# DDR3.net
KiCad netlist of a schematic drawn in Altium Designer
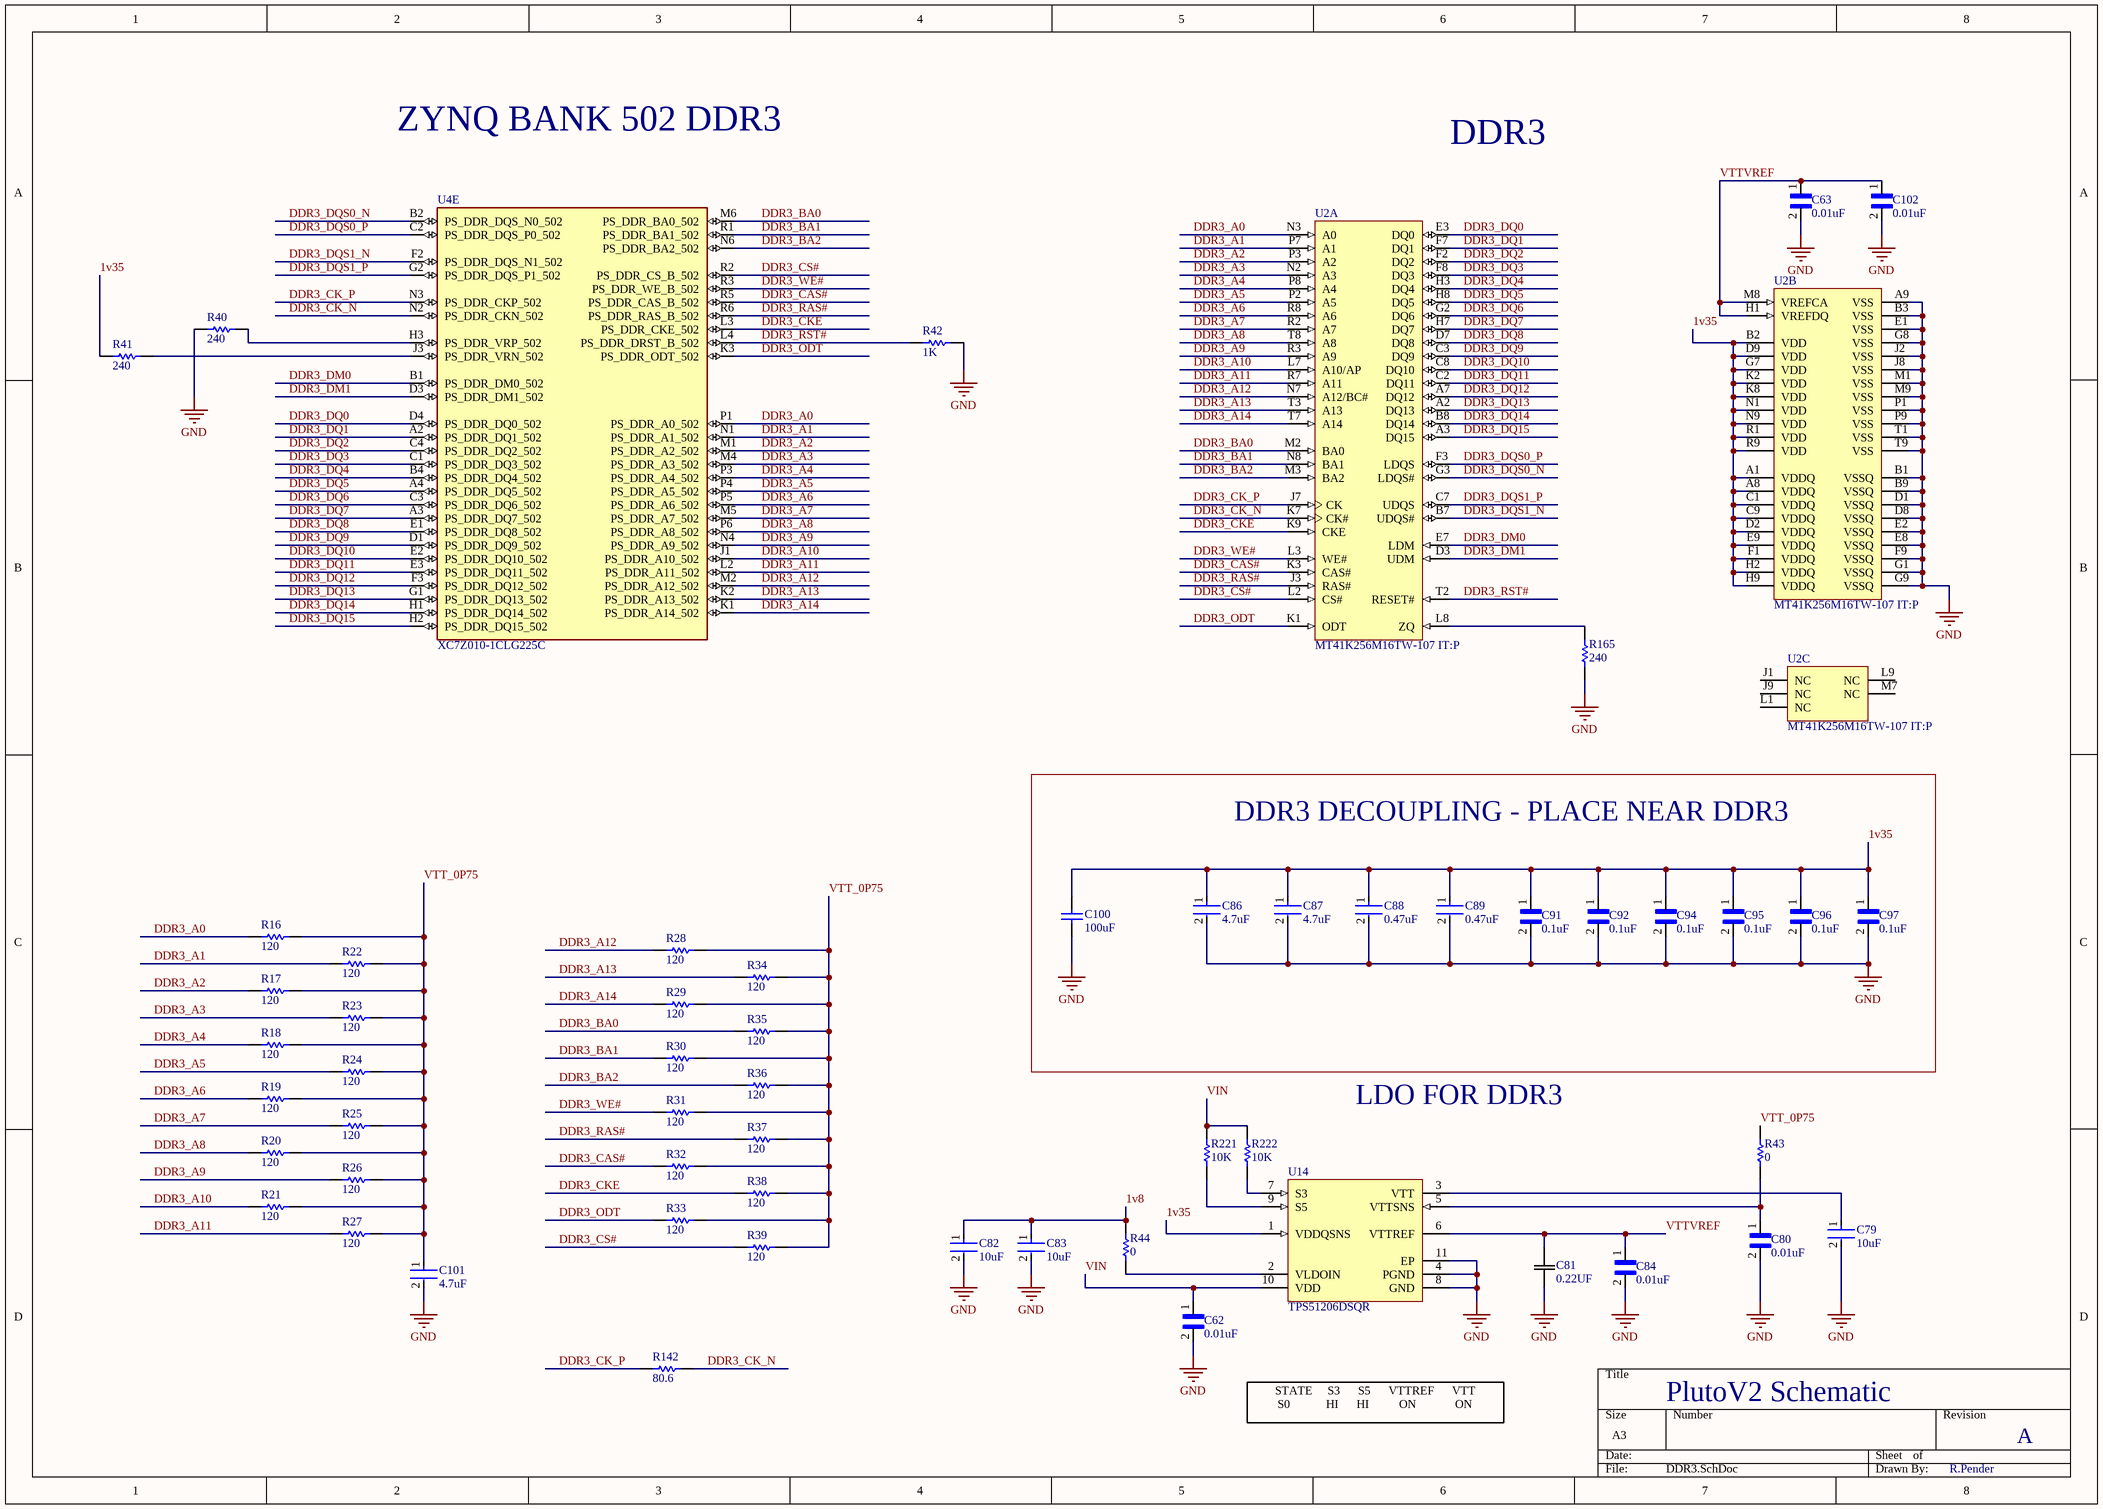
[diagram p0: DDR3.SchDoc]

(export (version "E")
  (design (tool "Eeschema 10.0.6"))
  (components
    (comp (ref "C62")
      (value "0.01uF")
      (footprint "CAPC0603X33N")
      (description "SMD Capacitor X7R(EIA) with Capacitance: 10000pF Tol. 10%. Rated Voltage: 10Vdc")
      (fields (field (name "MP") "GRM033R71A103KA01D") (field (name "MF") "Murata"))
      (libsource (lib "GRM033R71A103KA01D") (part "GRM033R71A103KA01D"))
    )
    (comp (ref "C63")
      (value "0.01uF")
      (footprint "CAPC0603X33N")
      (description "SMD Capacitor X7R(EIA) with Capacitance: 10000pF Tol. 10%. Rated Voltage: 10Vdc")
      (fields (field (name "MP") "GRM033R71A103KA01D") (field (name "MF") "Murata"))
      (libsource (lib "GRM033R71A103KA01D") (part "GRM033R71A103KA01D"))
    )
    (comp (ref "C79")
      (value "10uF")
      (footprint "FP-GRM188-0_1-e0_2_0_55-IPC_A")
      (description "Chip Multilayer Ceramic Capacitors for General Purpose, 0603, 10uF, X5R, 15%, 20%, 6.3V")
      (fields (field (name "VOLTAGE") "6.3V") (field (name "TOLERANCE") "20%"))
      (libsource (lib "Altium Content Vault") (part "02cd4be3c70576c341d710602a673aa"))
    )
    (comp (ref "C80")
      (value "0.01uF")
      (footprint "CAPC0603X33N")
      (description "SMD Capacitor X7R(EIA) with Capacitance: 10000pF Tol. 10%. Rated Voltage: 10Vdc")
      (fields (field (name "MP") "GRM033R71A103KA01D") (field (name "MF") "Murata"))
      (libsource (lib "GRM033R71A103KA01D") (part "GRM033R71A103KA01D"))
    )
    (comp (ref "C81")
      (value "0.22UF")
      (footprint "CAP_U_0805_KNO")
      (description "No Description Available")
      (fields
        (field (name "MANUFACTURER_PART_NUMBER") "080530250224KXT")
        (field (name "COPYRIGHT") "Copyright (C) 2022 Ultra Librarian. All rights reserved.")
      )
      (libsource (lib "080530250224KXT") (part "080530250224KXT"))
    )
    (comp (ref "C82")
      (value "10uF")
      (footprint "FP-GRM188-0_1-e0_2_0_55-IPC_A")
      (description "Chip Multilayer Ceramic Capacitors for General Purpose, 0603, 10uF, X5R, 15%, 20%, 6.3V")
      (fields (field (name "VOLTAGE") "6.3V") (field (name "TOLERANCE") "20%"))
      (libsource (lib "Altium Content Vault") (part "02cd4be3c70576c341d710602a673aa"))
    )
    (comp (ref "C83")
      (value "10uF")
      (footprint "FP-GRM188-0_1-e0_2_0_55-IPC_A")
      (description "Chip Multilayer Ceramic Capacitors for General Purpose, 0603, 10uF, X5R, 15%, 20%, 6.3V")
      (fields (field (name "VOLTAGE") "6.3V") (field (name "TOLERANCE") "20%"))
      (libsource (lib "Altium Content Vault") (part "02cd4be3c70576c341d710602a673aa"))
    )
    (comp (ref "C84")
      (value "0.01uF")
      (footprint "CAPC0603X33N")
      (description "SMD Capacitor X7R(EIA) with Capacitance: 10000pF Tol. 10%. Rated Voltage: 10Vdc")
      (fields (field (name "MP") "GRM033R71A103KA01D") (field (name "MF") "Murata"))
      (libsource (lib "GRM033R71A103KA01D") (part "GRM033R71A103KA01D"))
    )
    (comp (ref "C86")
      (value "4.7uF")
      (footprint "FP-C1005-050-0_15-MFG")
      (description "CAP CER 4.7UF 6.3V X5R 0402")
      (fields (field (name "VOLTAGE") "6.3V") (field (name "TOLERANCE") "10%"))
      (libsource (lib "Altium Content Vault") (part "02cd4be3c70576c341d710602a673aa"))
    )
    (comp (ref "C87")
      (value "4.7uF")
      (footprint "FP-C1005-050-0_15-MFG")
      (description "CAP CER 4.7UF 6.3V X5R 0402")
      (fields (field (name "VOLTAGE") "6.3V") (field (name "TOLERANCE") "10%"))
      (libsource (lib "Altium Content Vault") (part "02cd4be3c70576c341d710602a673aa"))
    )
    (comp (ref "C88")
      (value "0.47uF")
      (footprint "FP-C1005-050-0_15-MFG")
      (description "CAP CER 4.7UF 6.3V X5R 0402")
      (fields (field (name "VOLTAGE") "6.3V") (field (name "TOLERANCE") "10%"))
      (libsource (lib "Altium Content Vault") (part "02cd4be3c70576c341d710602a673aa"))
    )
    (comp (ref "C89")
      (value "0.47uF")
      (footprint "FP-C1005-050-0_15-MFG")
      (description "CAP CER 4.7UF 6.3V X5R 0402")
      (fields (field (name "VOLTAGE") "6.3V") (field (name "TOLERANCE") "10%"))
      (libsource (lib "Altium Content Vault") (part "02cd4be3c70576c341d710602a673aa"))
    )
    (comp (ref "C91")
      (value "0.1uF")
      (footprint "CAPC0603X33N")
      (description "CAP 0.1UF 16VDC X5R 20% SMD 0201 PAPER TAPE")
      (fields (field (name "MP") "GRM033R61C104ME84D"))
      (libsource (lib "GRM033R61C104ME84D") (part "GRM033R61C104ME84D"))
    )
    (comp (ref "C92")
      (value "0.1uF")
      (footprint "CAPC0603X33N")
      (description "CAP 0.1UF 16VDC X5R 20% SMD 0201 PAPER TAPE")
      (fields (field (name "MP") "GRM033R61C104ME84D"))
      (libsource (lib "GRM033R61C104ME84D") (part "GRM033R61C104ME84D"))
    )
    (comp (ref "C94")
      (value "0.1uF")
      (footprint "CAPC0603X33N")
      (description "CAP 0.1UF 16VDC X5R 20% SMD 0201 PAPER TAPE")
      (fields (field (name "MP") "GRM033R61C104ME84D"))
      (libsource (lib "GRM033R61C104ME84D") (part "GRM033R61C104ME84D"))
    )
    (comp (ref "C95")
      (value "0.1uF")
      (footprint "CAPC0603X33N")
      (description "CAP 0.1UF 16VDC X5R 20% SMD 0201 PAPER TAPE")
      (fields (field (name "MP") "GRM033R61C104ME84D"))
      (libsource (lib "GRM033R61C104ME84D") (part "GRM033R61C104ME84D"))
    )
    (comp (ref "C96")
      (value "0.1uF")
      (footprint "CAPC0603X33N")
      (description "CAP 0.1UF 16VDC X5R 20% SMD 0201 PAPER TAPE")
      (fields (field (name "MP") "GRM033R61C104ME84D"))
      (libsource (lib "GRM033R61C104ME84D") (part "GRM033R61C104ME84D"))
    )
    (comp (ref "C97")
      (value "0.1uF")
      (footprint "CAPC0603X33N")
      (description "CAP 0.1UF 16VDC X5R 20% SMD 0201 PAPER TAPE")
      (fields (field (name "MP") "GRM033R61C104ME84D"))
      (libsource (lib "GRM033R61C104ME84D") (part "GRM033R61C104ME84D"))
    )
    (comp (ref "C100")
      (value "100uF")
      (footprint "CAPC3216X190X55ML30T25")
      (description "Chip Capacitor, 100 uF, +/- 20%, 6.3 V, -55 to 85 degC, 1206 (3216 Metric), RoHS, Tape and Reel")
      (fields (field (name "TOLERANCE") "20%") (field (name "PARTNUMBER") "GRM31CR60J107ME39L"))
      (libsource (lib "Altium Content Vault") (part "CAP-NP-2"))
    )
    (comp (ref "C101")
      (value "4.7uF")
      (footprint "FP-C1005-050-0_15-MFG")
      (description "CAP CER 4.7UF 6.3V X5R 0402")
      (fields (field (name "VOLTAGE") "6.3V") (field (name "TOLERANCE") "10%"))
      (libsource (lib "Altium Content Vault") (part "02cd4be3c70576c341d710602a673aa"))
    )
    (comp (ref "C102")
      (value "0.01uF")
      (footprint "CAPC0603X33N")
      (description "SMD Capacitor X7R(EIA) with Capacitance: 10000pF Tol. 10%. Rated Voltage: 10Vdc")
      (fields (field (name "MP") "GRM033R71A103KA01D") (field (name "MF") "Murata"))
      (libsource (lib "GRM033R71A103KA01D") (part "GRM033R71A103KA01D"))
    )
    (comp (ref "R16")
      (value "120")
      (footprint "1-0201")
      (description "Thick Film Chip Resistor, 10 Ohm to 1M Ohm Range, 5% Tolerance, 0201 Size, 0.05 W")
      (fields (field (name "PUBLISHER") "Altium Limited"))
      (libsource (lib "Panasonic Resistor") (part "ERJ1GE"))
    )
    (comp (ref "R17")
      (value "120")
      (footprint "1-0201")
      (description "Thick Film Chip Resistor, 10 Ohm to 1M Ohm Range, 5% Tolerance, 0201 Size, 0.05 W")
      (fields (field (name "PUBLISHER") "Altium Limited"))
      (libsource (lib "Panasonic Resistor") (part "ERJ1GE"))
    )
    (comp (ref "R18")
      (value "120")
      (footprint "1-0201")
      (description "Thick Film Chip Resistor, 10 Ohm to 1M Ohm Range, 5% Tolerance, 0201 Size, 0.05 W")
      (fields (field (name "PUBLISHER") "Altium Limited"))
      (libsource (lib "Panasonic Resistor") (part "ERJ1GE"))
    )
    (comp (ref "R19")
      (value "120")
      (footprint "1-0201")
      (description "Thick Film Chip Resistor, 10 Ohm to 1M Ohm Range, 5% Tolerance, 0201 Size, 0.05 W")
      (fields (field (name "PUBLISHER") "Altium Limited"))
      (libsource (lib "Panasonic Resistor") (part "ERJ1GE"))
    )
    (comp (ref "R20")
      (value "120")
      (footprint "1-0201")
      (description "Thick Film Chip Resistor, 10 Ohm to 1M Ohm Range, 5% Tolerance, 0201 Size, 0.05 W")
      (fields (field (name "PUBLISHER") "Altium Limited"))
      (libsource (lib "Panasonic Resistor") (part "ERJ1GE"))
    )
    (comp (ref "R21")
      (value "120")
      (footprint "1-0201")
      (description "Thick Film Chip Resistor, 10 Ohm to 1M Ohm Range, 5% Tolerance, 0201 Size, 0.05 W")
      (fields (field (name "PUBLISHER") "Altium Limited"))
      (libsource (lib "Panasonic Resistor") (part "ERJ1GE"))
    )
    (comp (ref "R22")
      (value "120")
      (footprint "1-0201")
      (description "Thick Film Chip Resistor, 10 Ohm to 1M Ohm Range, 5% Tolerance, 0201 Size, 0.05 W")
      (fields (field (name "PUBLISHER") "Altium Limited"))
      (libsource (lib "Panasonic Resistor") (part "ERJ1GE"))
    )
    (comp (ref "R23")
      (value "120")
      (footprint "1-0201")
      (description "Thick Film Chip Resistor, 10 Ohm to 1M Ohm Range, 5% Tolerance, 0201 Size, 0.05 W")
      (fields (field (name "PUBLISHER") "Altium Limited"))
      (libsource (lib "Panasonic Resistor") (part "ERJ1GE"))
    )
    (comp (ref "R24")
      (value "120")
      (footprint "1-0201")
      (description "Thick Film Chip Resistor, 10 Ohm to 1M Ohm Range, 5% Tolerance, 0201 Size, 0.05 W")
      (fields (field (name "PUBLISHER") "Altium Limited"))
      (libsource (lib "Panasonic Resistor") (part "ERJ1GE"))
    )
    (comp (ref "R25")
      (value "120")
      (footprint "1-0201")
      (description "Thick Film Chip Resistor, 10 Ohm to 1M Ohm Range, 5% Tolerance, 0201 Size, 0.05 W")
      (fields (field (name "PUBLISHER") "Altium Limited"))
      (libsource (lib "Panasonic Resistor") (part "ERJ1GE"))
    )
    (comp (ref "R26")
      (value "120")
      (footprint "1-0201")
      (description "Thick Film Chip Resistor, 10 Ohm to 1M Ohm Range, 5% Tolerance, 0201 Size, 0.05 W")
      (fields (field (name "PUBLISHER") "Altium Limited"))
      (libsource (lib "Panasonic Resistor") (part "ERJ1GE"))
    )
    (comp (ref "R27")
      (value "120")
      (footprint "1-0201")
      (description "Thick Film Chip Resistor, 10 Ohm to 1M Ohm Range, 5% Tolerance, 0201 Size, 0.05 W")
      (fields (field (name "PUBLISHER") "Altium Limited"))
      (libsource (lib "Panasonic Resistor") (part "ERJ1GE"))
    )
    (comp (ref "R28")
      (value "120")
      (footprint "1-0201")
      (description "Thick Film Chip Resistor, 10 Ohm to 1M Ohm Range, 5% Tolerance, 0201 Size, 0.05 W")
      (fields (field (name "PUBLISHER") "Altium Limited"))
      (libsource (lib "Panasonic Resistor") (part "ERJ1GE"))
    )
    (comp (ref "R29")
      (value "120")
      (footprint "1-0201")
      (description "Thick Film Chip Resistor, 10 Ohm to 1M Ohm Range, 5% Tolerance, 0201 Size, 0.05 W")
      (fields (field (name "PUBLISHER") "Altium Limited"))
      (libsource (lib "Panasonic Resistor") (part "ERJ1GE"))
    )
    (comp (ref "R30")
      (value "120")
      (footprint "1-0201")
      (description "Thick Film Chip Resistor, 10 Ohm to 1M Ohm Range, 5% Tolerance, 0201 Size, 0.05 W")
      (fields (field (name "PUBLISHER") "Altium Limited"))
      (libsource (lib "Panasonic Resistor") (part "ERJ1GE"))
    )
    (comp (ref "R31")
      (value "120")
      (footprint "1-0201")
      (description "Thick Film Chip Resistor, 10 Ohm to 1M Ohm Range, 5% Tolerance, 0201 Size, 0.05 W")
      (fields (field (name "PUBLISHER") "Altium Limited"))
      (libsource (lib "Panasonic Resistor") (part "ERJ1GE"))
    )
    (comp (ref "R32")
      (value "120")
      (footprint "1-0201")
      (description "Thick Film Chip Resistor, 10 Ohm to 1M Ohm Range, 5% Tolerance, 0201 Size, 0.05 W")
      (fields (field (name "PUBLISHER") "Altium Limited"))
      (libsource (lib "Panasonic Resistor") (part "ERJ1GE"))
    )
    (comp (ref "R33")
      (value "120")
      (footprint "1-0201")
      (description "Thick Film Chip Resistor, 10 Ohm to 1M Ohm Range, 5% Tolerance, 0201 Size, 0.05 W")
      (fields (field (name "PUBLISHER") "Altium Limited"))
      (libsource (lib "Panasonic Resistor") (part "ERJ1GE"))
    )
    (comp (ref "R34")
      (value "120")
      (footprint "1-0201")
      (description "Thick Film Chip Resistor, 10 Ohm to 1M Ohm Range, 5% Tolerance, 0201 Size, 0.05 W")
      (fields (field (name "PUBLISHER") "Altium Limited"))
      (libsource (lib "Panasonic Resistor") (part "ERJ1GE"))
    )
    (comp (ref "R35")
      (value "120")
      (footprint "1-0201")
      (description "Thick Film Chip Resistor, 10 Ohm to 1M Ohm Range, 5% Tolerance, 0201 Size, 0.05 W")
      (fields (field (name "PUBLISHER") "Altium Limited"))
      (libsource (lib "Panasonic Resistor") (part "ERJ1GE"))
    )
    (comp (ref "R36")
      (value "120")
      (footprint "1-0201")
      (description "Thick Film Chip Resistor, 10 Ohm to 1M Ohm Range, 5% Tolerance, 0201 Size, 0.05 W")
      (fields (field (name "PUBLISHER") "Altium Limited"))
      (libsource (lib "Panasonic Resistor") (part "ERJ1GE"))
    )
    (comp (ref "R37")
      (value "120")
      (footprint "1-0201")
      (description "Thick Film Chip Resistor, 10 Ohm to 1M Ohm Range, 5% Tolerance, 0201 Size, 0.05 W")
      (fields (field (name "PUBLISHER") "Altium Limited"))
      (libsource (lib "Panasonic Resistor") (part "ERJ1GE"))
    )
    (comp (ref "R38")
      (value "120")
      (footprint "1-0201")
      (description "Thick Film Chip Resistor, 10 Ohm to 1M Ohm Range, 5% Tolerance, 0201 Size, 0.05 W")
      (fields (field (name "PUBLISHER") "Altium Limited"))
      (libsource (lib "Panasonic Resistor") (part "ERJ1GE"))
    )
    (comp (ref "R39")
      (value "120")
      (footprint "1-0201")
      (description "Thick Film Chip Resistor, 10 Ohm to 1M Ohm Range, 5% Tolerance, 0201 Size, 0.05 W")
      (fields (field (name "PUBLISHER") "Altium Limited"))
      (libsource (lib "Panasonic Resistor") (part "ERJ1GE"))
    )
    (comp (ref "R40")
      (value "240")
      (footprint "2-0402")
      (fields (field (name "PUBLISHER") "Altium Limited"))
      (libsource (lib "Panasonic Resistor") (part "ERJ2RK"))
    )
    (comp (ref "R41")
      (value "240")
      (footprint "2-0402")
      (fields (field (name "PUBLISHER") "Altium Limited"))
      (libsource (lib "Panasonic Resistor") (part "ERJ2RK"))
    )
    (comp (ref "R42")
      (value "1K")
      (footprint "2-0402")
      (fields (field (name "PUBLISHER") "Altium Limited"))
      (libsource (lib "Panasonic Resistor") (part "ERJ2RK"))
    )
    (comp (ref "R43")
      (value "0")
      (footprint "RESC1005X40X25NL10T10")
      (fields (field (name "PART NUMBER") "MC00625W040210R") (field (name "MANUFACTURER") "Multicomp"))
      (libsource (lib "Altium Content Vault") (part "RES"))
    )
    (comp (ref "R44")
      (value "0")
      (footprint "RESC1005X40X25NL10T10")
      (fields (field (name "PART NUMBER") "MC00625W040210R") (field (name "MANUFACTURER") "Multicomp"))
      (libsource (lib "Altium Content Vault") (part "RES"))
    )
    (comp (ref "R142")
      (value "80.6")
      (footprint "2-0402")
      (fields (field (name "PUBLISHER") "Altium Limited"))
      (libsource (lib "Panasonic Resistor") (part "ERJ2RK"))
    )
    (comp (ref "R165")
      (value "240")
      (footprint "2-0402")
      (fields (field (name "PUBLISHER") "Altium Limited"))
      (libsource (lib "Panasonic Resistor") (part "ERJ2RK"))
    )
    (comp (ref "R221")
      (value "10K")
      (footprint "2-0402")
      (fields (field (name "PUBLISHER") "Altium Limited"))
      (libsource (lib "Panasonic Resistor") (part "ERJ2RK"))
    )
    (comp (ref "R222")
      (value "10K")
      (footprint "2-0402")
      (fields (field (name "PUBLISHER") "Altium Limited"))
      (libsource (lib "Panasonic Resistor") (part "ERJ2RK"))
    )
    (comp (ref "U2")
      (value "MT41K256M16TW-107 IT:P")
      (footprint "MICT-TW-96")
      (description "Automotive DDR3L SDRAM, 4 GB, 933 MHz, 1.283 to 1.45 V, -40 to 95 degC, 96-Pin TFBGA, RoHS, Tray")
      (fields (field (name "MANUFACTURER") "Micron"))
      (libsource (lib "Components - 26.05.22 - 21.32") (part "CMP-2000-06773-2"))
    )
    (comp (ref "U4")
      (value "XC7Z010-1CLG225C")
      (footprint "BGA225C80P15X15_1300X1300X150")
      (fields (field (name "MF") "Xilinx Inc.") (field (name "DIGI-KEY_PART_NUMBER") "122-1855-ND"))
      (libsource (lib "XC7Z010-1CLG225C") (part "XC7Z010-1CLG225C"))
    )
    (comp (ref "U14")
      (value "TPS51206DSQR")
      (footprint "DSQ0010A_V")
      (fields (field (name "MANUFACTURER") "Texas Instruments"))
      (libsource (lib "Altium Content Vault") (part "TI-TPS51206DSQ10-1500X900TP"))
    )
  )
  (nets
    (net (code "1") (name "/1v8") (class "Default")
      (node (ref "C82") (pin "1") (pinfunction "1_1") (pintype "passive"))
      (node (ref "C83") (pin "1") (pinfunction "1_1") (pintype "passive"))
      (node (ref "R44") (pin "1") (pinfunction "1_1") (pintype "passive"))
    )
    (net (code "2") (name "/1v35") (class "Default")
      (node (ref "C100") (pin "1") (pinfunction "1_1") (pintype "passive"))
      (node (ref "C86") (pin "1") (pinfunction "1_1") (pintype "passive"))
      (node (ref "C87") (pin "1") (pinfunction "1_1") (pintype "passive"))
      (node (ref "C88") (pin "1") (pinfunction "1_1") (pintype "passive"))
      (node (ref "C89") (pin "1") (pinfunction "1_1") (pintype "passive"))
      (node (ref "C91") (pin "1") (pinfunction "1_1") (pintype "passive"))
      (node (ref "C92") (pin "1") (pinfunction "1_1") (pintype "passive"))
      (node (ref "C94") (pin "1") (pinfunction "1_1") (pintype "passive"))
      (node (ref "C95") (pin "1") (pinfunction "1_1") (pintype "passive"))
      (node (ref "C96") (pin "1") (pinfunction "1_1") (pintype "passive"))
      (node (ref "C97") (pin "1") (pinfunction "1_1") (pintype "passive"))
      (node (ref "R41") (pin "1") (pinfunction "1_1") (pintype "passive"))
      (node (ref "U14") (pin "1") (pinfunction "VDDQSNS_1") (pintype "input"))
      (node (ref "U2") (pin "A1") (pinfunction "VDDQ_A1") (pintype "power_in"))
      (node (ref "U2") (pin "A8") (pinfunction "VDDQ_A8") (pintype "power_in"))
      (node (ref "U2") (pin "B2") (pinfunction "VDD_B2") (pintype "power_in"))
      (node (ref "U2") (pin "C1") (pinfunction "VDDQ_C1") (pintype "power_in"))
      (node (ref "U2") (pin "C9") (pinfunction "VDDQ_C9") (pintype "power_in"))
      (node (ref "U2") (pin "D2") (pinfunction "VDDQ_D2") (pintype "power_in"))
      (node (ref "U2") (pin "D9") (pinfunction "VDD_D9") (pintype "power_in"))
      (node (ref "U2") (pin "E9") (pinfunction "VDDQ_E9") (pintype "power_in"))
      (node (ref "U2") (pin "F1") (pinfunction "VDDQ_F1") (pintype "power_in"))
      (node (ref "U2") (pin "G7") (pinfunction "VDD_G7") (pintype "power_in"))
      (node (ref "U2") (pin "H2") (pinfunction "VDDQ_H2") (pintype "power_in"))
      (node (ref "U2") (pin "H9") (pinfunction "VDDQ_H9") (pintype "power_in"))
      (node (ref "U2") (pin "K2") (pinfunction "VDD_K2") (pintype "power_in"))
      (node (ref "U2") (pin "K8") (pinfunction "VDD_K8") (pintype "power_in"))
      (node (ref "U2") (pin "N1") (pinfunction "VDD_N1") (pintype "power_in"))
      (node (ref "U2") (pin "N9") (pinfunction "VDD_N9") (pintype "power_in"))
      (node (ref "U2") (pin "R1") (pinfunction "VDD_R1") (pintype "power_in"))
      (node (ref "U2") (pin "R9") (pinfunction "VDD_R9") (pintype "power_in"))
    )
    (net (code "3") (name "/DDR3_A0") (class "Default")
      (node (ref "R16") (pin "1") (pinfunction "1_1") (pintype "passive"))
      (node (ref "U2") (pin "N3") (pinfunction "A0_N3") (pintype "input"))
      (node (ref "U4") (pin "P1") (pinfunction "PS_DDR_A0_502_P1") (pintype "bidirectional"))
    )
    (net (code "4") (name "/DDR3_A1") (class "Default")
      (node (ref "R22") (pin "1") (pinfunction "1_1") (pintype "passive"))
      (node (ref "U2") (pin "P7") (pinfunction "A1_P7") (pintype "input"))
      (node (ref "U4") (pin "N1") (pinfunction "PS_DDR_A1_502_N1") (pintype "bidirectional"))
    )
    (net (code "5") (name "/DDR3_A2") (class "Default")
      (node (ref "R17") (pin "1") (pinfunction "1_1") (pintype "passive"))
      (node (ref "U2") (pin "P3") (pinfunction "A2_P3") (pintype "input"))
      (node (ref "U4") (pin "M1") (pinfunction "PS_DDR_A2_502_M1") (pintype "bidirectional"))
    )
    (net (code "6") (name "/DDR3_A3") (class "Default")
      (node (ref "R23") (pin "1") (pinfunction "1_1") (pintype "passive"))
      (node (ref "U2") (pin "N2") (pinfunction "A3_N2") (pintype "input"))
      (node (ref "U4") (pin "M4") (pinfunction "PS_DDR_A3_502_M4") (pintype "bidirectional"))
    )
    (net (code "7") (name "/DDR3_A4") (class "Default")
      (node (ref "R18") (pin "1") (pinfunction "1_1") (pintype "passive"))
      (node (ref "U2") (pin "P8") (pinfunction "A4_P8") (pintype "input"))
      (node (ref "U4") (pin "P3") (pinfunction "PS_DDR_A4_502_P3") (pintype "bidirectional"))
    )
    (net (code "8") (name "/DDR3_A5") (class "Default")
      (node (ref "R24") (pin "1") (pinfunction "1_1") (pintype "passive"))
      (node (ref "U2") (pin "P2") (pinfunction "A5_P2") (pintype "input"))
      (node (ref "U4") (pin "P4") (pinfunction "PS_DDR_A5_502_P4") (pintype "bidirectional"))
    )
    (net (code "9") (name "/DDR3_A6") (class "Default")
      (node (ref "R19") (pin "1") (pinfunction "1_1") (pintype "passive"))
      (node (ref "U2") (pin "R8") (pinfunction "A6_R8") (pintype "input"))
      (node (ref "U4") (pin "P5") (pinfunction "PS_DDR_A6_502_P5") (pintype "bidirectional"))
    )
    (net (code "10") (name "/DDR3_A7") (class "Default")
      (node (ref "R25") (pin "1") (pinfunction "1_1") (pintype "passive"))
      (node (ref "U2") (pin "R2") (pinfunction "A7_R2") (pintype "input"))
      (node (ref "U4") (pin "M5") (pinfunction "PS_DDR_A7_502_M5") (pintype "bidirectional"))
    )
    (net (code "11") (name "/DDR3_A8") (class "Default")
      (node (ref "R20") (pin "1") (pinfunction "1_1") (pintype "passive"))
      (node (ref "U2") (pin "T8") (pinfunction "A8_T8") (pintype "input"))
      (node (ref "U4") (pin "P6") (pinfunction "PS_DDR_A8_502_P6") (pintype "bidirectional"))
    )
    (net (code "12") (name "/DDR3_A9") (class "Default")
      (node (ref "R26") (pin "1") (pinfunction "1_1") (pintype "passive"))
      (node (ref "U2") (pin "R3") (pinfunction "A9_R3") (pintype "input"))
      (node (ref "U4") (pin "N4") (pinfunction "PS_DDR_A9_502_N4") (pintype "bidirectional"))
    )
    (net (code "13") (name "/DDR3_A10") (class "Default")
      (node (ref "R21") (pin "1") (pinfunction "1_1") (pintype "passive"))
      (node (ref "U2") (pin "L7") (pinfunction "A10/AP_L7") (pintype "input"))
      (node (ref "U4") (pin "J1") (pinfunction "PS_DDR_A10_502_J1") (pintype "bidirectional"))
    )
    (net (code "14") (name "/DDR3_A11") (class "Default")
      (node (ref "R27") (pin "1") (pinfunction "1_1") (pintype "passive"))
      (node (ref "U2") (pin "R7") (pinfunction "A11_R7") (pintype "input"))
      (node (ref "U4") (pin "L2") (pinfunction "PS_DDR_A11_502_L2") (pintype "bidirectional"))
    )
    (net (code "15") (name "/DDR3_A12") (class "Default")
      (node (ref "R28") (pin "1") (pinfunction "1_1") (pintype "passive"))
      (node (ref "U2") (pin "N7") (pinfunction "A12/BC#_N7") (pintype "input"))
      (node (ref "U4") (pin "M2") (pinfunction "PS_DDR_A12_502_M2") (pintype "bidirectional"))
    )
    (net (code "16") (name "/DDR3_A13") (class "Default")
      (node (ref "R34") (pin "1") (pinfunction "1_1") (pintype "passive"))
      (node (ref "U2") (pin "T3") (pinfunction "A13_T3") (pintype "input"))
      (node (ref "U4") (pin "K2") (pinfunction "PS_DDR_A13_502_K2") (pintype "bidirectional"))
    )
    (net (code "17") (name "/DDR3_A14") (class "Default")
      (node (ref "R29") (pin "1") (pinfunction "1_1") (pintype "passive"))
      (node (ref "U2") (pin "T7") (pinfunction "A14_T7") (pintype "input"))
      (node (ref "U4") (pin "K1") (pinfunction "PS_DDR_A14_502_K1") (pintype "bidirectional"))
    )
    (net (code "18") (name "/DDR3_BA0") (class "Default")
      (node (ref "R35") (pin "1") (pinfunction "1_1") (pintype "passive"))
      (node (ref "U2") (pin "M2") (pinfunction "BA0_M2") (pintype "input"))
      (node (ref "U4") (pin "M6") (pinfunction "PS_DDR_BA0_502_M6") (pintype "bidirectional"))
    )
    (net (code "19") (name "/DDR3_BA1") (class "Default")
      (node (ref "R30") (pin "1") (pinfunction "1_1") (pintype "passive"))
      (node (ref "U2") (pin "N8") (pinfunction "BA1_N8") (pintype "input"))
      (node (ref "U4") (pin "R1") (pinfunction "PS_DDR_BA1_502_R1") (pintype "bidirectional"))
    )
    (net (code "20") (name "/DDR3_BA2") (class "Default")
      (node (ref "R36") (pin "1") (pinfunction "1_1") (pintype "passive"))
      (node (ref "U2") (pin "M3") (pinfunction "BA2_M3") (pintype "input"))
      (node (ref "U4") (pin "N6") (pinfunction "PS_DDR_BA2_502_N6") (pintype "bidirectional"))
    )
    (net (code "21") (name "/DDR3_CAS#") (class "Default")
      (node (ref "R32") (pin "1") (pinfunction "1_1") (pintype "passive"))
      (node (ref "U2") (pin "K3") (pinfunction "CAS#_K3") (pintype "input"))
      (node (ref "U4") (pin "R5") (pinfunction "PS_DDR_CAS_B_502_R5") (pintype "bidirectional"))
    )
    (net (code "22") (name "/DDR3_CKE") (class "Default")
      (node (ref "R38") (pin "1") (pinfunction "1_1") (pintype "passive"))
      (node (ref "U2") (pin "K9") (pinfunction "CKE_K9") (pintype "input"))
      (node (ref "U4") (pin "L3") (pinfunction "PS_DDR_CKE_502_L3") (pintype "bidirectional"))
    )
    (net (code "23") (name "/DDR3_CK_N") (class "Default")
      (node (ref "R142") (pin "2") (pinfunction "2_2") (pintype "passive"))
      (node (ref "U2") (pin "K7") (pinfunction "CK#_K7") (pintype "input"))
      (node (ref "U4") (pin "N2") (pinfunction "PS_DDR_CKN_502_N2") (pintype "bidirectional"))
    )
    (net (code "24") (name "/DDR3_CK_P") (class "Default")
      (node (ref "R142") (pin "1") (pinfunction "1_1") (pintype "passive"))
      (node (ref "U2") (pin "J7") (pinfunction "CK_J7") (pintype "input"))
      (node (ref "U4") (pin "N3") (pinfunction "PS_DDR_CKP_502_N3") (pintype "bidirectional"))
    )
    (net (code "25") (name "/DDR3_CS#") (class "Default")
      (node (ref "R39") (pin "1") (pinfunction "1_1") (pintype "passive"))
      (node (ref "U2") (pin "L2") (pinfunction "CS#_L2") (pintype "input"))
      (node (ref "U4") (pin "R2") (pinfunction "PS_DDR_CS_B_502_R2") (pintype "bidirectional"))
    )
    (net (code "26") (name "/DDR3_DM0") (class "Default")
      (node (ref "U2") (pin "E7") (pinfunction "LDM_E7") (pintype "input"))
      (node (ref "U4") (pin "B1") (pinfunction "PS_DDR_DM0_502_B1") (pintype "bidirectional"))
    )
    (net (code "27") (name "/DDR3_DM1") (class "Default")
      (node (ref "U2") (pin "D3") (pinfunction "UDM_D3") (pintype "input"))
      (node (ref "U4") (pin "D3") (pinfunction "PS_DDR_DM1_502_D3") (pintype "bidirectional"))
    )
    (net (code "28") (name "/DDR3_DQ0") (class "Default")
      (node (ref "U2") (pin "E3") (pinfunction "DQ0_E3") (pintype "bidirectional"))
      (node (ref "U4") (pin "D4") (pinfunction "PS_DDR_DQ0_502_D4") (pintype "bidirectional"))
    )
    (net (code "29") (name "/DDR3_DQ1") (class "Default")
      (node (ref "U2") (pin "F7") (pinfunction "DQ1_F7") (pintype "bidirectional"))
      (node (ref "U4") (pin "A2") (pinfunction "PS_DDR_DQ1_502_A2") (pintype "bidirectional"))
    )
    (net (code "30") (name "/DDR3_DQ2") (class "Default")
      (node (ref "U2") (pin "F2") (pinfunction "DQ2_F2") (pintype "bidirectional"))
      (node (ref "U4") (pin "C4") (pinfunction "PS_DDR_DQ2_502_C4") (pintype "bidirectional"))
    )
    (net (code "31") (name "/DDR3_DQ3") (class "Default")
      (node (ref "U2") (pin "F8") (pinfunction "DQ3_F8") (pintype "bidirectional"))
      (node (ref "U4") (pin "C1") (pinfunction "PS_DDR_DQ3_502_C1") (pintype "bidirectional"))
    )
    (net (code "32") (name "/DDR3_DQ4") (class "Default")
      (node (ref "U2") (pin "H3") (pinfunction "DQ4_H3") (pintype "bidirectional"))
      (node (ref "U4") (pin "B4") (pinfunction "PS_DDR_DQ4_502_B4") (pintype "bidirectional"))
    )
    (net (code "33") (name "/DDR3_DQ5") (class "Default")
      (node (ref "U2") (pin "H8") (pinfunction "DQ5_H8") (pintype "bidirectional"))
      (node (ref "U4") (pin "A4") (pinfunction "PS_DDR_DQ5_502_A4") (pintype "bidirectional"))
    )
    (net (code "34") (name "/DDR3_DQ6") (class "Default")
      (node (ref "U2") (pin "G2") (pinfunction "DQ6_G2") (pintype "bidirectional"))
      (node (ref "U4") (pin "C3") (pinfunction "PS_DDR_DQ6_502_C3") (pintype "bidirectional"))
    )
    (net (code "35") (name "/DDR3_DQ7") (class "Default")
      (node (ref "U2") (pin "H7") (pinfunction "DQ7_H7") (pintype "bidirectional"))
      (node (ref "U4") (pin "A3") (pinfunction "PS_DDR_DQ7_502_A3") (pintype "bidirectional"))
    )
    (net (code "36") (name "/DDR3_DQ8") (class "Default")
      (node (ref "U2") (pin "D7") (pinfunction "DQ8_D7") (pintype "bidirectional"))
      (node (ref "U4") (pin "E1") (pinfunction "PS_DDR_DQ8_502_E1") (pintype "bidirectional"))
    )
    (net (code "37") (name "/DDR3_DQ9") (class "Default")
      (node (ref "U2") (pin "C3") (pinfunction "DQ9_C3") (pintype "bidirectional"))
      (node (ref "U4") (pin "D1") (pinfunction "PS_DDR_DQ9_502_D1") (pintype "bidirectional"))
    )
    (net (code "38") (name "/DDR3_DQ10") (class "Default")
      (node (ref "U2") (pin "C8") (pinfunction "DQ10_C8") (pintype "bidirectional"))
      (node (ref "U4") (pin "E2") (pinfunction "PS_DDR_DQ10_502_E2") (pintype "bidirectional"))
    )
    (net (code "39") (name "/DDR3_DQ11") (class "Default")
      (node (ref "U2") (pin "C2") (pinfunction "DQ11_C2") (pintype "bidirectional"))
      (node (ref "U4") (pin "E3") (pinfunction "PS_DDR_DQ11_502_E3") (pintype "bidirectional"))
    )
    (net (code "40") (name "/DDR3_DQ12") (class "Default")
      (node (ref "U2") (pin "A7") (pinfunction "DQ12_A7") (pintype "bidirectional"))
      (node (ref "U4") (pin "F3") (pinfunction "PS_DDR_DQ12_502_F3") (pintype "bidirectional"))
    )
    (net (code "41") (name "/DDR3_DQ13") (class "Default")
      (node (ref "U2") (pin "A2") (pinfunction "DQ13_A2") (pintype "bidirectional"))
      (node (ref "U4") (pin "G1") (pinfunction "PS_DDR_DQ13_502_G1") (pintype "bidirectional"))
    )
    (net (code "42") (name "/DDR3_DQ14") (class "Default")
      (node (ref "U2") (pin "B8") (pinfunction "DQ14_B8") (pintype "bidirectional"))
      (node (ref "U4") (pin "H1") (pinfunction "PS_DDR_DQ14_502_H1") (pintype "bidirectional"))
    )
    (net (code "43") (name "/DDR3_DQ15") (class "Default")
      (node (ref "U2") (pin "A3") (pinfunction "DQ15_A3") (pintype "bidirectional"))
      (node (ref "U4") (pin "H2") (pinfunction "PS_DDR_DQ15_502_H2") (pintype "bidirectional"))
    )
    (net (code "44") (name "/DDR3_DQS0_N") (class "Default")
      (node (ref "U2") (pin "G3") (pinfunction "LDQS#_G3") (pintype "bidirectional"))
      (node (ref "U4") (pin "B2") (pinfunction "PS_DDR_DQS_N0_502_B2") (pintype "bidirectional"))
    )
    (net (code "45") (name "/DDR3_DQS0_P") (class "Default")
      (node (ref "U2") (pin "F3") (pinfunction "LDQS_F3") (pintype "bidirectional"))
      (node (ref "U4") (pin "C2") (pinfunction "PS_DDR_DQS_P0_502_C2") (pintype "bidirectional"))
    )
    (net (code "46") (name "/DDR3_DQS1_N") (class "Default")
      (node (ref "U2") (pin "B7") (pinfunction "UDQS#_B7") (pintype "bidirectional"))
      (node (ref "U4") (pin "F2") (pinfunction "PS_DDR_DQS_N1_502_F2") (pintype "bidirectional"))
    )
    (net (code "47") (name "/DDR3_DQS1_P") (class "Default")
      (node (ref "U2") (pin "C7") (pinfunction "UDQS_C7") (pintype "bidirectional"))
      (node (ref "U4") (pin "G2") (pinfunction "PS_DDR_DQS_P1_502_G2") (pintype "bidirectional"))
    )
    (net (code "48") (name "/DDR3_ODT") (class "Default")
      (node (ref "R33") (pin "1") (pinfunction "1_1") (pintype "passive"))
      (node (ref "U2") (pin "K1") (pinfunction "ODT_K1") (pintype "input"))
      (node (ref "U4") (pin "K3") (pinfunction "PS_DDR_ODT_502_K3") (pintype "bidirectional"))
    )
    (net (code "49") (name "/DDR3_RAS#") (class "Default")
      (node (ref "R37") (pin "1") (pinfunction "1_1") (pintype "passive"))
      (node (ref "U2") (pin "J3") (pinfunction "RAS#_J3") (pintype "input"))
      (node (ref "U4") (pin "R6") (pinfunction "PS_DDR_RAS_B_502_R6") (pintype "bidirectional"))
    )
    (net (code "50") (name "/DDR3_RST#") (class "Default")
      (node (ref "R42") (pin "1") (pinfunction "1_1") (pintype "passive"))
      (node (ref "U2") (pin "T2") (pinfunction "RESET#_T2") (pintype "input"))
      (node (ref "U4") (pin "L4") (pinfunction "PS_DDR_DRST_B_502_L4") (pintype "bidirectional"))
    )
    (net (code "51") (name "/DDR3_WE#") (class "Default")
      (node (ref "R31") (pin "1") (pinfunction "1_1") (pintype "passive"))
      (node (ref "U2") (pin "L3") (pinfunction "WE#_L3") (pintype "input"))
      (node (ref "U4") (pin "R3") (pinfunction "PS_DDR_WE_B_502_R3") (pintype "bidirectional"))
    )
    (net (code "52") (name "/VIN") (class "Default")
      (node (ref "C62") (pin "1") (pinfunction "1_1") (pintype "passive"))
      (node (ref "R221") (pin "1") (pinfunction "1_1") (pintype "passive"))
      (node (ref "R222") (pin "1") (pinfunction "1_1") (pintype "passive"))
      (node (ref "U14") (pin "10") (pinfunction "VDD_10") (pintype "power_in"))
    )
    (net (code "53") (name "/VTTVREF") (class "Default")
      (node (ref "C102") (pin "1") (pinfunction "1_1") (pintype "passive"))
      (node (ref "C63") (pin "1") (pinfunction "1_1") (pintype "passive"))
      (node (ref "C81") (pin "1") (pinfunction "1_1") (pintype "passive"))
      (node (ref "C84") (pin "1") (pinfunction "1_1") (pintype "passive"))
      (node (ref "U14") (pin "6") (pinfunction "VTTREF_6") (pintype "power_in"))
      (node (ref "U2") (pin "H1") (pinfunction "VREFDQ_H1") (pintype "input"))
      (node (ref "U2") (pin "M8") (pinfunction "VREFCA_M8") (pintype "input"))
    )
    (net (code "54") (name "/VTT_0P75") (class "Default")
      (node (ref "C101") (pin "1") (pinfunction "1_1") (pintype "passive"))
      (node (ref "R16") (pin "2") (pinfunction "2_2") (pintype "passive"))
      (node (ref "R17") (pin "2") (pinfunction "2_2") (pintype "passive"))
      (node (ref "R18") (pin "2") (pinfunction "2_2") (pintype "passive"))
      (node (ref "R19") (pin "2") (pinfunction "2_2") (pintype "passive"))
      (node (ref "R20") (pin "2") (pinfunction "2_2") (pintype "passive"))
      (node (ref "R21") (pin "2") (pinfunction "2_2") (pintype "passive"))
      (node (ref "R22") (pin "2") (pinfunction "2_2") (pintype "passive"))
      (node (ref "R23") (pin "2") (pinfunction "2_2") (pintype "passive"))
      (node (ref "R24") (pin "2") (pinfunction "2_2") (pintype "passive"))
      (node (ref "R25") (pin "2") (pinfunction "2_2") (pintype "passive"))
      (node (ref "R26") (pin "2") (pinfunction "2_2") (pintype "passive"))
      (node (ref "R27") (pin "2") (pinfunction "2_2") (pintype "passive"))
      (node (ref "R28") (pin "2") (pinfunction "2_2") (pintype "passive"))
      (node (ref "R29") (pin "2") (pinfunction "2_2") (pintype "passive"))
      (node (ref "R30") (pin "2") (pinfunction "2_2") (pintype "passive"))
      (node (ref "R31") (pin "2") (pinfunction "2_2") (pintype "passive"))
      (node (ref "R32") (pin "2") (pinfunction "2_2") (pintype "passive"))
      (node (ref "R33") (pin "2") (pinfunction "2_2") (pintype "passive"))
      (node (ref "R34") (pin "2") (pinfunction "2_2") (pintype "passive"))
      (node (ref "R35") (pin "2") (pinfunction "2_2") (pintype "passive"))
      (node (ref "R36") (pin "2") (pinfunction "2_2") (pintype "passive"))
      (node (ref "R37") (pin "2") (pinfunction "2_2") (pintype "passive"))
      (node (ref "R38") (pin "2") (pinfunction "2_2") (pintype "passive"))
      (node (ref "R39") (pin "2") (pinfunction "2_2") (pintype "passive"))
      (node (ref "R43") (pin "1") (pinfunction "1_1") (pintype "passive"))
    )
    (net (code "55") (name "GND") (class "Default")
      (node (ref "C100") (pin "2") (pinfunction "2_2") (pintype "passive"))
      (node (ref "C101") (pin "2") (pinfunction "2_2") (pintype "passive"))
      (node (ref "C102") (pin "2") (pinfunction "2_2") (pintype "passive"))
      (node (ref "C62") (pin "2") (pinfunction "2_2") (pintype "passive"))
      (node (ref "C63") (pin "2") (pinfunction "2_2") (pintype "passive"))
      (node (ref "C79") (pin "2") (pinfunction "2_2") (pintype "passive"))
      (node (ref "C80") (pin "2") (pinfunction "2_2") (pintype "passive"))
      (node (ref "C81") (pin "2") (pinfunction "2_2") (pintype "passive"))
      (node (ref "C82") (pin "2") (pinfunction "2_2") (pintype "passive"))
      (node (ref "C83") (pin "2") (pinfunction "2_2") (pintype "passive"))
      (node (ref "C84") (pin "2") (pinfunction "2_2") (pintype "passive"))
      (node (ref "C86") (pin "2") (pinfunction "2_2") (pintype "passive"))
      (node (ref "C87") (pin "2") (pinfunction "2_2") (pintype "passive"))
      (node (ref "C88") (pin "2") (pinfunction "2_2") (pintype "passive"))
      (node (ref "C89") (pin "2") (pinfunction "2_2") (pintype "passive"))
      (node (ref "C91") (pin "2") (pinfunction "2_2") (pintype "passive"))
      (node (ref "C92") (pin "2") (pinfunction "2_2") (pintype "passive"))
      (node (ref "C94") (pin "2") (pinfunction "2_2") (pintype "passive"))
      (node (ref "C95") (pin "2") (pinfunction "2_2") (pintype "passive"))
      (node (ref "C96") (pin "2") (pinfunction "2_2") (pintype "passive"))
      (node (ref "C97") (pin "2") (pinfunction "2_2") (pintype "passive"))
      (node (ref "R165") (pin "2") (pinfunction "2_2") (pintype "passive"))
      (node (ref "R40") (pin "1") (pinfunction "1_1") (pintype "passive"))
      (node (ref "R42") (pin "2") (pinfunction "2_2") (pintype "passive"))
      (node (ref "U14") (pin "11") (pinfunction "EP_11") (pintype "power_in"))
      (node (ref "U14") (pin "4") (pinfunction "PGND_4") (pintype "power_in"))
      (node (ref "U14") (pin "8") (pinfunction "GND_8") (pintype "power_in"))
      (node (ref "U2") (pin "A9") (pinfunction "VSS_A9") (pintype "power_in"))
      (node (ref "U2") (pin "B1") (pinfunction "VSSQ_B1") (pintype "power_in"))
      (node (ref "U2") (pin "B3") (pinfunction "VSS_B3") (pintype "power_in"))
      (node (ref "U2") (pin "B9") (pinfunction "VSSQ_B9") (pintype "power_in"))
      (node (ref "U2") (pin "D1") (pinfunction "VSSQ_D1") (pintype "power_in"))
      (node (ref "U2") (pin "D8") (pinfunction "VSSQ_D8") (pintype "power_in"))
      (node (ref "U2") (pin "E1") (pinfunction "VSS_E1") (pintype "power_in"))
      (node (ref "U2") (pin "E2") (pinfunction "VSSQ_E2") (pintype "power_in"))
      (node (ref "U2") (pin "E8") (pinfunction "VSSQ_E8") (pintype "power_in"))
      (node (ref "U2") (pin "F9") (pinfunction "VSSQ_F9") (pintype "power_in"))
      (node (ref "U2") (pin "G1") (pinfunction "VSSQ_G1") (pintype "power_in"))
      (node (ref "U2") (pin "G8") (pinfunction "VSS_G8") (pintype "power_in"))
      (node (ref "U2") (pin "G9") (pinfunction "VSSQ_G9") (pintype "power_in"))
      (node (ref "U2") (pin "J2") (pinfunction "VSS_J2") (pintype "power_in"))
      (node (ref "U2") (pin "J8") (pinfunction "VSS_J8") (pintype "power_in"))
      (node (ref "U2") (pin "M1") (pinfunction "VSS_M1") (pintype "power_in"))
      (node (ref "U2") (pin "M9") (pinfunction "VSS_M9") (pintype "power_in"))
      (node (ref "U2") (pin "P1") (pinfunction "VSS_P1") (pintype "power_in"))
      (node (ref "U2") (pin "P9") (pinfunction "VSS_P9") (pintype "power_in"))
      (node (ref "U2") (pin "T1") (pinfunction "VSS_T1") (pintype "power_in"))
      (node (ref "U2") (pin "T9") (pinfunction "VSS_T9") (pintype "power_in"))
    )
    (net (code "56") (name "Net-(U2A-ZQ)") (class "Default")
      (node (ref "R165") (pin "1") (pinfunction "1_1") (pintype "passive"))
      (node (ref "U2") (pin "L8") (pinfunction "ZQ_L8") (pintype "input"))
    )
    (net (code "57") (name "Net-(U4E-PS_DDR_VRN_502)") (class "Default")
      (node (ref "R41") (pin "2") (pinfunction "2_2") (pintype "passive"))
      (node (ref "U4") (pin "J3") (pinfunction "PS_DDR_VRN_502_J3") (pintype "bidirectional"))
    )
    (net (code "58") (name "Net-(U4E-PS_DDR_VRP_502)") (class "Default")
      (node (ref "R40") (pin "2") (pinfunction "2_2") (pintype "passive"))
      (node (ref "U4") (pin "H3") (pinfunction "PS_DDR_VRP_502_H3") (pintype "bidirectional"))
    )
    (net (code "59") (name "Net-(U14-S3)") (class "Default")
      (node (ref "R222") (pin "2") (pinfunction "2_2") (pintype "passive"))
      (node (ref "U14") (pin "7") (pinfunction "S3_7") (pintype "input"))
    )
    (net (code "60") (name "Net-(U14-S5)") (class "Default")
      (node (ref "R221") (pin "2") (pinfunction "2_2") (pintype "passive"))
      (node (ref "U14") (pin "9") (pinfunction "S5_9") (pintype "input"))
    )
    (net (code "61") (name "Net-(U14-VLDOIN)") (class "Default")
      (node (ref "R44") (pin "2") (pinfunction "2_2") (pintype "passive"))
      (node (ref "U14") (pin "2") (pinfunction "VLDOIN_2") (pintype "power_in"))
    )
    (net (code "62") (name "Net-(U14-VTT)") (class "Default")
      (node (ref "C79") (pin "1") (pinfunction "1_1") (pintype "passive"))
      (node (ref "U14") (pin "3") (pinfunction "VTT_3") (pintype "power_in"))
    )
    (net (code "63") (name "Net-(U14-VTTSNS)") (class "Default")
      (node (ref "C80") (pin "1") (pinfunction "1_1") (pintype "passive"))
      (node (ref "R43") (pin "2") (pinfunction "2_2") (pintype "passive"))
      (node (ref "U14") (pin "5") (pinfunction "VTTSNS_5") (pintype "input"))
    )
    (net (code "64") (name "unconnected-(U2C-NC-PadJ1)") (class "Default")
      (node (ref "U2") (pin "J1") (pinfunction "NC_J1") (pintype "passive"))
    )
    (net (code "65") (name "unconnected-(U2C-NC-PadJ9)") (class "Default")
      (node (ref "U2") (pin "J9") (pinfunction "NC_J9") (pintype "passive"))
    )
    (net (code "66") (name "unconnected-(U2C-NC-PadL1)") (class "Default")
      (node (ref "U2") (pin "L1") (pinfunction "NC_L1") (pintype "passive"))
    )
    (net (code "67") (name "unconnected-(U2C-NC-PadL9)") (class "Default")
      (node (ref "U2") (pin "L9") (pinfunction "NC_L9") (pintype "passive"))
    )
    (net (code "68") (name "unconnected-(U2C-NC-PadM7)") (class "Default")
      (node (ref "U2") (pin "M7") (pinfunction "NC_M7") (pintype "passive"))
    )
  )
)
